# 05_USART.net
KiCad netlist of a schematic drawn in Altium Designer
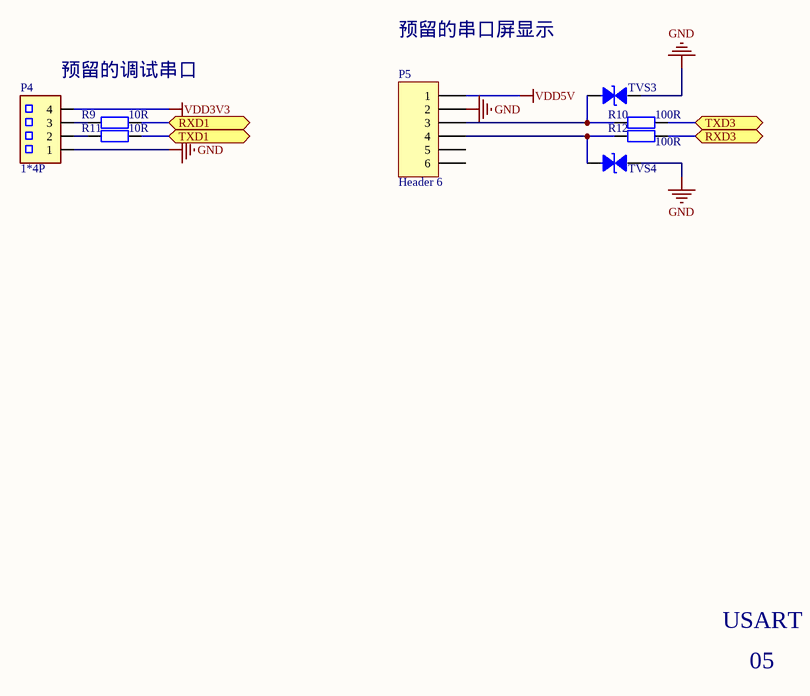
[diagram p0: 05_USART.SchDoc]

(export (version "E")
  (design (tool "Eeschema 10.0.6"))
  (components
    (comp (ref "P4") (value "1*4P") (footprint "XH2.54-4A") (libsource (lib "PARK-N5 V1.0") (part "HDR1*4")))
    (comp (ref "P5")
      (value "Header 6")
      (footprint "6X2MMZ")
      (description "Header, 6-Pin")
      (fields (field (name "PUBLISHER") "Altium Limited"))
      (libsource (lib "Miscellaneous Connectors") (part "Header 6"))
    )
    (comp (ref "R9")
      (value "10R")
      (footprint "SMD-0603")
      (description "贴片电阻 5%")
      (libsource (lib "XiaoyI") (part "RES2"))
    )
    (comp (ref "R10")
      (value "100R")
      (footprint "SMD-0603")
      (description "贴片电阻 5%")
      (libsource (lib "XiaoyI") (part "RES2"))
    )
    (comp (ref "R11")
      (value "10R")
      (footprint "SMD-0603")
      (description "贴片电阻 5%")
      (libsource (lib "XiaoyI") (part "RES2"))
    )
    (comp (ref "R12")
      (value "100R")
      (footprint "SMD-0603")
      (description "贴片电阻 5%")
      (libsource (lib "XiaoyI") (part "RES2"))
    )
    (comp (ref "TVS3")
      (value "ESD5Z5.0CT1G")
      (footprint "SOD-523")
      (description "TVS")
      (libsource (lib "XiaoyI") (part "TVS-1"))
    )
    (comp (ref "TVS4")
      (value "ESD5Z5.0CT1G")
      (footprint "SOD-523")
      (description "TVS")
      (libsource (lib "XiaoyI") (part "TVS-1"))
    )
  )
  (nets
    (net (code "1") (name "/RXD1") (class "Default")
      (node (ref "R9") (pin "2") (pinfunction "2_2") (pintype "passive"))
    )
    (net (code "2") (name "/RXD3") (class "Default")
      (node (ref "R12") (pin "2") (pinfunction "2_2") (pintype "passive"))
    )
    (net (code "3") (name "/TXD1") (class "Default")
      (node (ref "R11") (pin "2") (pinfunction "2_2") (pintype "passive"))
    )
    (net (code "4") (name "/TXD3") (class "Default")
      (node (ref "R10") (pin "2") (pinfunction "2_2") (pintype "passive"))
    )
    (net (code "5") (name "GND") (class "Default")
      (node (ref "P4") (pin "1") (pinfunction "1_1") (pintype "passive"))
      (node (ref "P5") (pin "2") (pinfunction "2_2") (pintype "passive"))
      (node (ref "TVS3") (pin "1") (pinfunction "A_1") (pintype "passive"))
      (node (ref "TVS4") (pin "1") (pinfunction "A_1") (pintype "passive"))
    )
    (net (code "6") (name "Net-(P4-Pad2)") (class "Default")
      (node (ref "P4") (pin "2") (pinfunction "2_2") (pintype "passive"))
      (node (ref "R11") (pin "1") (pinfunction "1_1") (pintype "passive"))
    )
    (net (code "7") (name "Net-(P4-Pad3)") (class "Default")
      (node (ref "P4") (pin "3") (pinfunction "3_3") (pintype "passive"))
      (node (ref "R9") (pin "1") (pinfunction "1_1") (pintype "passive"))
    )
    (net (code "8") (name "Net-(TVS3-B)") (class "Default")
      (node (ref "P5") (pin "3") (pinfunction "3_3") (pintype "passive"))
      (node (ref "R10") (pin "1") (pinfunction "1_1") (pintype "passive"))
      (node (ref "TVS3") (pin "2") (pinfunction "B_2") (pintype "passive"))
    )
    (net (code "9") (name "Net-(TVS4-B)") (class "Default")
      (node (ref "P5") (pin "4") (pinfunction "4_4") (pintype "passive"))
      (node (ref "R12") (pin "1") (pinfunction "1_1") (pintype "passive"))
      (node (ref "TVS4") (pin "2") (pinfunction "B_2") (pintype "passive"))
    )
    (net (code "10") (name "VDD3V3") (class "Default")
      (node (ref "P4") (pin "4") (pinfunction "4_4") (pintype "passive"))
    )
    (net (code "11") (name "VDD5V") (class "Default")
      (node (ref "P5") (pin "1") (pinfunction "1_1") (pintype "passive"))
    )
    (net (code "12") (name "unconnected-(P5-Pad5)") (class "Default")
      (node (ref "P5") (pin "5") (pinfunction "5_5") (pintype "passive"))
    )
    (net (code "13") (name "unconnected-(P5-Pad6)") (class "Default")
      (node (ref "P5") (pin "6") (pinfunction "6_6") (pintype "passive"))
    )
  )
)
